# Black_Sesame.net
KiCad netlist of a schematic drawn in EAGLE
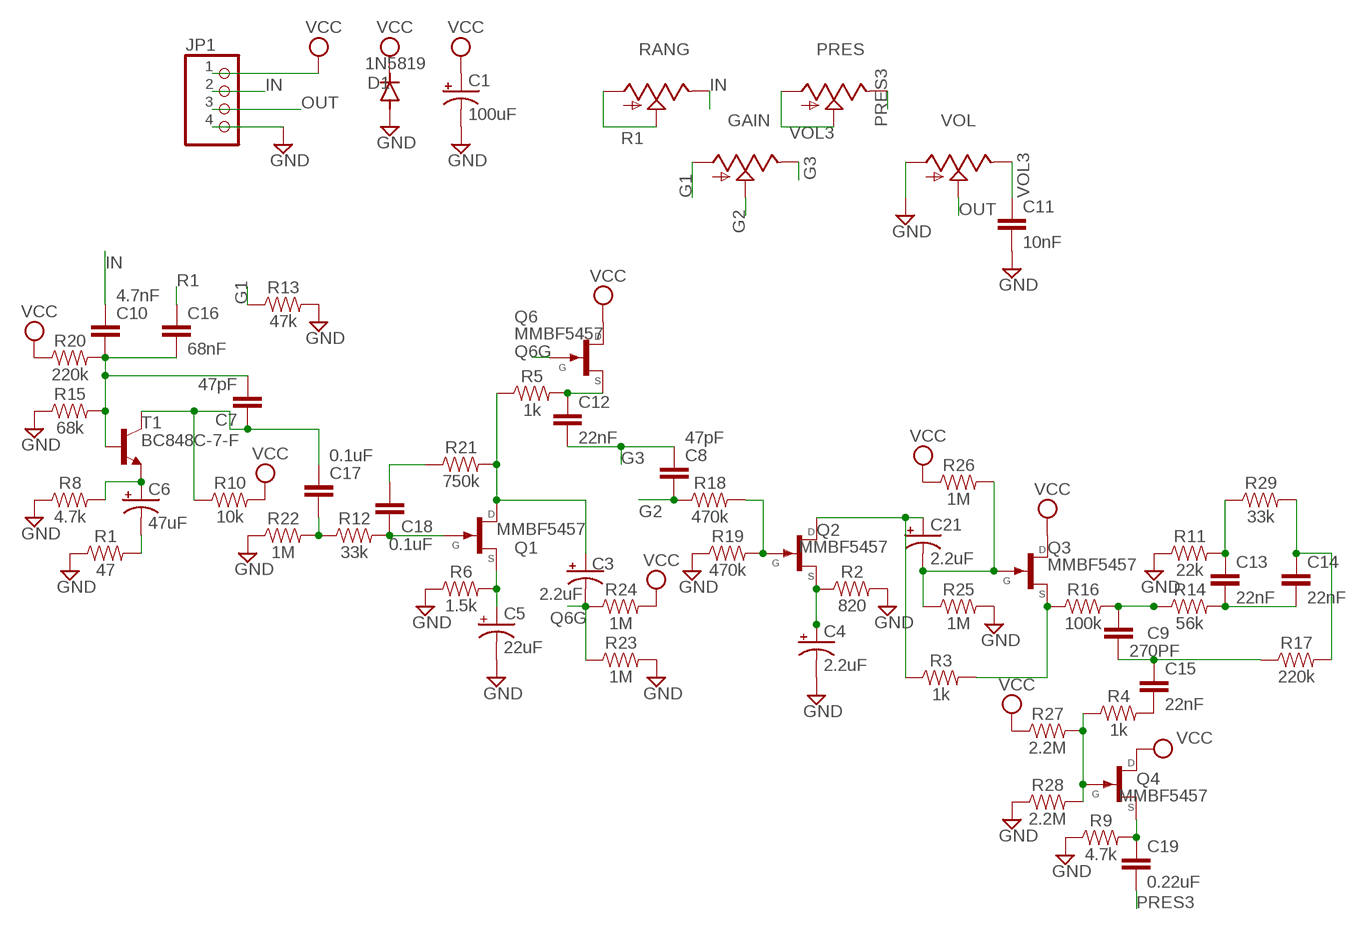
[diagram p0: schematic, sheet 1]

(export (version "E")
  (design (tool "Eeschema 10.0.6"))
  (components
    (comp (ref "C1")
      (value "100uF")
      (footprint "eagle-import:PAN_B_SMD+THRU")
      (libsource (lib "eagle-import") (part "CAP_SMD+THRUPAN_B"))
    )
    (comp (ref "C3")
      (value "2.2uF")
      (footprint "eagle-import:PAN_B_SMD+THRU")
      (libsource (lib "eagle-import") (part "CAP_SMD+THRUPAN_B"))
    )
    (comp (ref "C4")
      (value "2.2uF")
      (footprint "eagle-import:PAN_B_SMD+THRU")
      (libsource (lib "eagle-import") (part "CAP_SMD+THRUPAN_B"))
    )
    (comp (ref "C5")
      (value "22uF")
      (footprint "eagle-import:PAN_B_SMD+THRU")
      (libsource (lib "eagle-import") (part "CAP_SMD+THRUPAN_B"))
    )
    (comp (ref "C6")
      (value "47uF")
      (footprint "eagle-import:PAN_B_SMD+THRU")
      (libsource (lib "eagle-import") (part "CAP_SMD+THRUPAN_B"))
    )
    (comp (ref "C7")
      (value "47pF")
      (footprint "eagle-import:0603")
      (libsource (lib "eagle-import") (part "47PF-0603-50V-5%"))
    )
    (comp (ref "C8")
      (value "47pF")
      (footprint "eagle-import:0603")
      (libsource (lib "eagle-import") (part "47PF-0603-50V-5%"))
    )
    (comp (ref "C9")
      (value "270PF")
      (footprint "eagle-import:0603")
      (libsource (lib "eagle-import") (part "270PF-0603-50V-5%"))
    )
    (comp (ref "C10")
      (value "4.7nF")
      (footprint "eagle-import:0603")
      (libsource (lib "eagle-import") (part "3.3NF-0603-100V-10%"))
    )
    (comp (ref "C11")
      (value "10nF")
      (footprint "eagle-import:0603")
      (libsource (lib "eagle-import") (part "10NF-0603-50V-10%"))
    )
    (comp (ref "C12")
      (value "22nF")
      (footprint "eagle-import:0603")
      (libsource (lib "eagle-import") (part "22NF/22,000PF-0603-50V-10%"))
    )
    (comp (ref "C13")
      (value "22nF")
      (footprint "eagle-import:0603")
      (libsource (lib "eagle-import") (part "22NF/22,000PF-0603-50V-10%"))
    )
    (comp (ref "C14")
      (value "22nF")
      (footprint "eagle-import:0603")
      (libsource (lib "eagle-import") (part "22NF/22,000PF-0603-50V-10%"))
    )
    (comp (ref "C15")
      (value "22nF")
      (footprint "eagle-import:0603")
      (libsource (lib "eagle-import") (part "22NF/22,000PF-0603-50V-10%"))
    )
    (comp (ref "C16")
      (value "68nF")
      (footprint "eagle-import:0603")
      (libsource (lib "eagle-import") (part "47NF-0603-25V-5%"))
    )
    (comp (ref "C17")
      (value "0.1uF")
      (footprint "eagle-import:0603")
      (libsource (lib "eagle-import") (part "0.1UF-0603-25V-(+80/-20%)"))
    )
    (comp (ref "C18")
      (value "0.1uF")
      (footprint "eagle-import:0603")
      (libsource (lib "eagle-import") (part "0.1UF-0603-25V-(+80/-20%)"))
    )
    (comp (ref "C19")
      (value "0.22uF")
      (footprint "eagle-import:0603")
      (libsource (lib "eagle-import") (part "0.22UF-0603-25V-10%"))
    )
    (comp (ref "C21")
      (value "2.2uF")
      (footprint "eagle-import:PAN_B_SMD+THRU")
      (libsource (lib "eagle-import") (part "CAP_SMD+THRUPAN_B"))
    )
    (comp (ref "D1")
      (value "1N5819")
      (footprint "eagle-import:SOD123")
      (libsource (lib "eagle-import") (part "DIODE-SOD123"))
    )
    (comp (ref "GAIN")
      (value "9MM_SNAP-IN_POT_")
      (footprint "eagle-import:9MM_SNAP-IN_POT")
      (libsource (lib "eagle-import") (part "9MM_SNAP-IN_POT_"))
    )
    (comp (ref "JP1")
      (value "PINHD-1X4")
      (footprint "eagle-import:1X04")
      (libsource (lib "eagle-import") (part "PINHD-1X4"))
    )
    (comp (ref "PRES")
      (value "9MM_SNAP-IN_POT_")
      (footprint "eagle-import:9MM_SNAP-IN_POT")
      (libsource (lib "eagle-import") (part "9MM_SNAP-IN_POT_"))
    )
    (comp (ref "Q1")
      (value "MMBF5457")
      (footprint "eagle-import:SOT23")
      (fields (field (name "MF") "ON Semiconductor"))
      (libsource (lib "eagle-import") (part "MMBF5457"))
    )
    (comp (ref "Q2")
      (value "MMBF5457")
      (footprint "eagle-import:SOT23")
      (fields (field (name "MF") "ON Semiconductor"))
      (libsource (lib "eagle-import") (part "MMBF5457"))
    )
    (comp (ref "Q3")
      (value "MMBF5457")
      (footprint "eagle-import:SOT23")
      (fields (field (name "MF") "ON Semiconductor"))
      (libsource (lib "eagle-import") (part "MMBF5457"))
    )
    (comp (ref "Q4")
      (value "MMBF5457")
      (footprint "eagle-import:SOT23")
      (fields (field (name "MF") "ON Semiconductor"))
      (libsource (lib "eagle-import") (part "MMBF5457"))
    )
    (comp (ref "Q6")
      (value "MMBF5457")
      (footprint "eagle-import:SOT23")
      (fields (field (name "MF") "ON Semiconductor"))
      (libsource (lib "eagle-import") (part "MMBF5457"))
    )
    (comp (ref "R1")
      (value "47")
      (footprint "eagle-import:0603")
      (libsource (lib "eagle-import") (part "47KOHM-0603-1/10W-1%"))
    )
    (comp (ref "R2")
      (value "820")
      (footprint "eagle-import:0603")
      (libsource (lib "eagle-import") (part "82OHM-0603-1/10W-1%"))
    )
    (comp (ref "R3")
      (value "1k")
      (footprint "eagle-import:0603")
      (libsource (lib "eagle-import") (part "1KOHM-0603-1/10W-1%"))
    )
    (comp (ref "R4")
      (value "1k")
      (footprint "eagle-import:0603")
      (libsource (lib "eagle-import") (part "1KOHM-0603-1/10W-1%"))
    )
    (comp (ref "R5")
      (value "1k")
      (footprint "eagle-import:0603")
      (libsource (lib "eagle-import") (part "1KOHM-0603-1/10W-1%"))
    )
    (comp (ref "R6")
      (value "1.5k")
      (footprint "eagle-import:0603")
      (libsource (lib "eagle-import") (part "1KOHM-0603-1/10W-1%"))
    )
    (comp (ref "R8")
      (value "4.7k")
      (footprint "eagle-import:0603")
      (libsource (lib "eagle-import") (part "4.7KOHM-0603-1/10W-1%"))
    )
    (comp (ref "R9")
      (value "4.7k")
      (footprint "eagle-import:0603")
      (libsource (lib "eagle-import") (part "4.7KOHM-0603-1/10W-1%"))
    )
    (comp (ref "R10")
      (value "10k")
      (footprint "eagle-import:0603")
      (libsource (lib "eagle-import") (part "10KOHM-0603-1/10W-1%"))
    )
    (comp (ref "R11")
      (value "22k")
      (footprint "eagle-import:0603")
      (libsource (lib "eagle-import") (part "22KOHM-0603-1/10W-1%"))
    )
    (comp (ref "R12")
      (value "33k")
      (footprint "eagle-import:0603")
      (libsource (lib "eagle-import") (part "33KOHM-0603-1/10W-1%"))
    )
    (comp (ref "R13")
      (value "47k")
      (footprint "eagle-import:0603")
      (libsource (lib "eagle-import") (part "47KOHM-0603-1/10W-1%"))
    )
    (comp (ref "R14")
      (value "56k")
      (footprint "eagle-import:0603")
      (libsource (lib "eagle-import") (part "62KOHM-0603-1/10W-5%"))
    )
    (comp (ref "R15")
      (value "68k")
      (footprint "eagle-import:0603")
      (libsource (lib "eagle-import") (part "68.1KOHM-0603-1/10W-1%"))
    )
    (comp (ref "R16")
      (value "100k")
      (footprint "eagle-import:0603")
      (libsource (lib "eagle-import") (part "100KOHM-0603-1/10W-1%"))
    )
    (comp (ref "R17")
      (value "220k")
      (footprint "eagle-import:0603")
      (libsource (lib "eagle-import") (part "220KOHM-0603-1/10W-1%"))
    )
    (comp (ref "R18")
      (value "470k")
      (footprint "eagle-import:0603")
      (libsource (lib "eagle-import") (part "470OHM-0603-1/10W-1%"))
    )
    (comp (ref "R19")
      (value "470k")
      (footprint "eagle-import:0603")
      (libsource (lib "eagle-import") (part "470OHM-0603-1/10W-1%"))
    )
    (comp (ref "R20")
      (value "220k")
      (footprint "eagle-import:0603")
      (libsource (lib "eagle-import") (part "220KOHM-0603-1/10W-1%"))
    )
    (comp (ref "R21")
      (value "750k")
      (footprint "eagle-import:0603")
      (libsource (lib "eagle-import") (part "750OHM-0603-1/10W-1%"))
    )
    (comp (ref "R22")
      (value "1M")
      (footprint "eagle-import:0603")
      (libsource (lib "eagle-import") (part "1MOHM-0603-1/4W-5%"))
    )
    (comp (ref "R23")
      (value "1M")
      (footprint "eagle-import:0603")
      (libsource (lib "eagle-import") (part "1MOHM-0603-1/4W-5%"))
    )
    (comp (ref "R24")
      (value "1M")
      (footprint "eagle-import:0603")
      (libsource (lib "eagle-import") (part "1MOHM-0603-1/4W-5%"))
    )
    (comp (ref "R25")
      (value "1M")
      (footprint "eagle-import:0603")
      (libsource (lib "eagle-import") (part "1MOHM-0603-1/4W-5%"))
    )
    (comp (ref "R26")
      (value "1M")
      (footprint "eagle-import:0603")
      (libsource (lib "eagle-import") (part "1MOHM-0603-1/4W-5%"))
    )
    (comp (ref "R27")
      (value "2.2M")
      (footprint "eagle-import:0603")
      (libsource (lib "eagle-import") (part "2.2OHM-0603-1/10W-5%"))
    )
    (comp (ref "R28")
      (value "2.2M")
      (footprint "eagle-import:0603")
      (libsource (lib "eagle-import") (part "2.2OHM-0603-1/10W-5%"))
    )
    (comp (ref "R29")
      (value "33k")
      (footprint "eagle-import:0603")
      (libsource (lib "eagle-import") (part "33KOHM-0603-1/10W-1%"))
    )
    (comp (ref "RANG")
      (value "9MM_SNAP-IN_POT_")
      (footprint "eagle-import:9MM_SNAP-IN_POT")
      (libsource (lib "eagle-import") (part "9MM_SNAP-IN_POT_"))
    )
    (comp (ref "T1")
      (value "BC848C-7-F")
      (footprint "eagle-import:SOT23-BEC")
      (libsource (lib "eagle-import") (part "-NPN-SOT23-BECBC817-16"))
    )
    (comp (ref "VOL")
      (value "9MM_SNAP-IN_POT_")
      (footprint "eagle-import:9MM_SNAP-IN_POT")
      (libsource (lib "eagle-import") (part "9MM_SNAP-IN_POT_"))
    )
  )
  (nets
    (net (code "1") (name "/G1") (class "Default")
      (node (ref "GAIN") (pin "1") (pinfunction "A_1") (pintype "passive"))
      (node (ref "R13") (pin "1") (pinfunction "1_1") (pintype "passive"))
    )
    (net (code "2") (name "/G2") (class "Default")
      (node (ref "C8") (pin "2") (pinfunction "2_2") (pintype "passive"))
      (node (ref "GAIN") (pin "2") (pinfunction "S_2") (pintype "passive"))
      (node (ref "R18") (pin "1") (pinfunction "1_1") (pintype "passive"))
    )
    (net (code "3") (name "/G3") (class "Default")
      (node (ref "C12") (pin "2") (pinfunction "2_2") (pintype "passive"))
      (node (ref "C8") (pin "1") (pinfunction "1_1") (pintype "passive"))
      (node (ref "GAIN") (pin "3") (pinfunction "E_3") (pintype "passive"))
    )
    (net (code "4") (name "/IN") (class "Default")
      (node (ref "C10") (pin "1") (pinfunction "1_1") (pintype "passive"))
      (node (ref "JP1") (pin "2") (pinfunction "2_2") (pintype "passive"))
      (node (ref "RANG") (pin "3") (pinfunction "E_3") (pintype "passive"))
    )
    (net (code "5") (name "/OUT") (class "Default")
      (node (ref "JP1") (pin "3") (pinfunction "3_3") (pintype "passive"))
      (node (ref "VOL") (pin "2") (pinfunction "S_2") (pintype "passive"))
    )
    (net (code "6") (name "/PRES3") (class "Default")
      (node (ref "C19") (pin "2") (pinfunction "2_2") (pintype "passive"))
      (node (ref "PRES") (pin "3") (pinfunction "E_3") (pintype "passive"))
    )
    (net (code "7") (name "/Q6G") (class "Default")
      (node (ref "C3") (pin "-") (pinfunction "-_-") (pintype "passive"))
      (node (ref "C3") (pin "--") (pinfunction "-_--") (pintype "passive"))
      (node (ref "Q6") (pin "3") (pinfunction "G_3") (pintype "passive"))
      (node (ref "R23") (pin "1") (pinfunction "1_1") (pintype "passive"))
      (node (ref "R24") (pin "1") (pinfunction "1_1") (pintype "passive"))
    )
    (net (code "8") (name "/R1") (class "Default")
      (node (ref "C16") (pin "1") (pinfunction "1_1") (pintype "passive"))
      (node (ref "RANG") (pin "1") (pinfunction "A_1") (pintype "passive"))
      (node (ref "RANG") (pin "2") (pinfunction "S_2") (pintype "passive"))
    )
    (net (code "9") (name "/VOL3") (class "Default")
      (node (ref "C11") (pin "1") (pinfunction "1_1") (pintype "passive"))
      (node (ref "PRES") (pin "1") (pinfunction "A_1") (pintype "passive"))
      (node (ref "PRES") (pin "2") (pinfunction "S_2") (pintype "passive"))
      (node (ref "VOL") (pin "3") (pinfunction "E_3") (pintype "passive"))
    )
    (net (code "10") (name "GND") (class "Default")
      (node (ref "C1") (pin "-") (pinfunction "-_-") (pintype "passive"))
      (node (ref "C1") (pin "--") (pinfunction "-_--") (pintype "passive"))
      (node (ref "C11") (pin "2") (pinfunction "2_2") (pintype "passive"))
      (node (ref "C4") (pin "-") (pinfunction "-_-") (pintype "passive"))
      (node (ref "C4") (pin "--") (pinfunction "-_--") (pintype "passive"))
      (node (ref "C5") (pin "-") (pinfunction "-_-") (pintype "passive"))
      (node (ref "C5") (pin "--") (pinfunction "-_--") (pintype "passive"))
      (node (ref "D1") (pin "A") (pinfunction "A_A") (pintype "passive"))
      (node (ref "JP1") (pin "4") (pinfunction "4_4") (pintype "passive"))
      (node (ref "R1") (pin "1") (pinfunction "1_1") (pintype "passive"))
      (node (ref "R11") (pin "1") (pinfunction "1_1") (pintype "passive"))
      (node (ref "R13") (pin "2") (pinfunction "2_2") (pintype "passive"))
      (node (ref "R15") (pin "1") (pinfunction "1_1") (pintype "passive"))
      (node (ref "R19") (pin "1") (pinfunction "1_1") (pintype "passive"))
      (node (ref "R2") (pin "2") (pinfunction "2_2") (pintype "passive"))
      (node (ref "R22") (pin "1") (pinfunction "1_1") (pintype "passive"))
      (node (ref "R23") (pin "2") (pinfunction "2_2") (pintype "passive"))
      (node (ref "R25") (pin "2") (pinfunction "2_2") (pintype "passive"))
      (node (ref "R28") (pin "1") (pinfunction "1_1") (pintype "passive"))
      (node (ref "R6") (pin "1") (pinfunction "1_1") (pintype "passive"))
      (node (ref "R8") (pin "1") (pinfunction "1_1") (pintype "passive"))
      (node (ref "R9") (pin "1") (pinfunction "1_1") (pintype "passive"))
      (node (ref "VOL") (pin "1") (pinfunction "A_1") (pintype "passive"))
    )
    (net (code "11") (name "Net-(C6-+-Pad++)") (class "Default")
      (node (ref "C6") (pin "+") (pinfunction "+_+") (pintype "passive"))
      (node (ref "C6") (pin "++") (pinfunction "+_++") (pintype "passive"))
      (node (ref "R8") (pin "2") (pinfunction "2_2") (pintype "passive"))
      (node (ref "T1") (pin "E") (pinfunction "E_E") (pintype "passive"))
    )
    (net (code "12") (name "Net-(C6---Pad--)") (class "Default")
      (node (ref "C6") (pin "-") (pinfunction "-_-") (pintype "passive"))
      (node (ref "C6") (pin "--") (pinfunction "-_--") (pintype "passive"))
      (node (ref "R1") (pin "2") (pinfunction "2_2") (pintype "passive"))
    )
    (net (code "13") (name "Net-(C9-Pad1)") (class "Default")
      (node (ref "C9") (pin "1") (pinfunction "1_1") (pintype "passive"))
      (node (ref "R14") (pin "1") (pinfunction "1_1") (pintype "passive"))
      (node (ref "R16") (pin "2") (pinfunction "2_2") (pintype "passive"))
    )
    (net (code "14") (name "Net-(C10-Pad2)") (class "Default")
      (node (ref "C10") (pin "2") (pinfunction "2_2") (pintype "passive"))
      (node (ref "C16") (pin "2") (pinfunction "2_2") (pintype "passive"))
      (node (ref "C7") (pin "2") (pinfunction "2_2") (pintype "passive"))
      (node (ref "R15") (pin "2") (pinfunction "2_2") (pintype "passive"))
      (node (ref "R20") (pin "2") (pinfunction "2_2") (pintype "passive"))
      (node (ref "T1") (pin "B") (pinfunction "B_B") (pintype "passive"))
    )
    (net (code "15") (name "Net-(C13-Pad1)") (class "Default")
      (node (ref "C13") (pin "1") (pinfunction "1_1") (pintype "passive"))
      (node (ref "R11") (pin "2") (pinfunction "2_2") (pintype "passive"))
      (node (ref "R29") (pin "1") (pinfunction "1_1") (pintype "passive"))
    )
    (net (code "16") (name "Net-(C13-Pad2)") (class "Default")
      (node (ref "C13") (pin "2") (pinfunction "2_2") (pintype "passive"))
      (node (ref "C14") (pin "2") (pinfunction "2_2") (pintype "passive"))
      (node (ref "R14") (pin "2") (pinfunction "2_2") (pintype "passive"))
    )
    (net (code "17") (name "Net-(C14-Pad1)") (class "Default")
      (node (ref "C14") (pin "1") (pinfunction "1_1") (pintype "passive"))
      (node (ref "R17") (pin "2") (pinfunction "2_2") (pintype "passive"))
      (node (ref "R29") (pin "2") (pinfunction "2_2") (pintype "passive"))
    )
    (net (code "18") (name "Net-(C15-Pad1)") (class "Default")
      (node (ref "C15") (pin "1") (pinfunction "1_1") (pintype "passive"))
      (node (ref "C9") (pin "2") (pinfunction "2_2") (pintype "passive"))
      (node (ref "R17") (pin "1") (pinfunction "1_1") (pintype "passive"))
    )
    (net (code "19") (name "Net-(C15-Pad2)") (class "Default")
      (node (ref "C15") (pin "2") (pinfunction "2_2") (pintype "passive"))
      (node (ref "R4") (pin "2") (pinfunction "2_2") (pintype "passive"))
    )
    (net (code "20") (name "Net-(C17-Pad1)") (class "Default")
      (node (ref "C17") (pin "1") (pinfunction "1_1") (pintype "passive"))
      (node (ref "C7") (pin "1") (pinfunction "1_1") (pintype "passive"))
      (node (ref "R10") (pin "1") (pinfunction "1_1") (pintype "passive"))
      (node (ref "T1") (pin "C") (pinfunction "C_C") (pintype "passive"))
    )
    (net (code "21") (name "Net-(C17-Pad2)") (class "Default")
      (node (ref "C17") (pin "2") (pinfunction "2_2") (pintype "passive"))
      (node (ref "R12") (pin "1") (pinfunction "1_1") (pintype "passive"))
      (node (ref "R22") (pin "2") (pinfunction "2_2") (pintype "passive"))
    )
    (net (code "22") (name "Net-(C18-Pad2)") (class "Default")
      (node (ref "C18") (pin "2") (pinfunction "2_2") (pintype "passive"))
      (node (ref "R21") (pin "1") (pinfunction "1_1") (pintype "passive"))
    )
    (net (code "23") (name "Net-(Q1-D)") (class "Default")
      (node (ref "C3") (pin "+") (pinfunction "+_+") (pintype "passive"))
      (node (ref "C3") (pin "++") (pinfunction "+_++") (pintype "passive"))
      (node (ref "Q1") (pin "1") (pinfunction "D_1") (pintype "passive"))
      (node (ref "R21") (pin "2") (pinfunction "2_2") (pintype "passive"))
      (node (ref "R5") (pin "1") (pinfunction "1_1") (pintype "passive"))
    )
    (net (code "24") (name "Net-(Q1-G)") (class "Default")
      (node (ref "C18") (pin "1") (pinfunction "1_1") (pintype "passive"))
      (node (ref "Q1") (pin "3") (pinfunction "G_3") (pintype "passive"))
      (node (ref "R12") (pin "2") (pinfunction "2_2") (pintype "passive"))
    )
    (net (code "25") (name "Net-(Q1-S)") (class "Default")
      (node (ref "C5") (pin "+") (pinfunction "+_+") (pintype "passive"))
      (node (ref "C5") (pin "++") (pinfunction "+_++") (pintype "passive"))
      (node (ref "Q1") (pin "2") (pinfunction "S_2") (pintype "passive"))
      (node (ref "R6") (pin "2") (pinfunction "2_2") (pintype "passive"))
    )
    (net (code "26") (name "Net-(Q2-D)") (class "Default")
      (node (ref "C21") (pin "+") (pinfunction "+_+") (pintype "passive"))
      (node (ref "C21") (pin "++") (pinfunction "+_++") (pintype "passive"))
      (node (ref "Q2") (pin "1") (pinfunction "D_1") (pintype "passive"))
      (node (ref "R3") (pin "1") (pinfunction "1_1") (pintype "passive"))
    )
    (net (code "27") (name "Net-(Q2-G)") (class "Default")
      (node (ref "Q2") (pin "3") (pinfunction "G_3") (pintype "passive"))
      (node (ref "R18") (pin "2") (pinfunction "2_2") (pintype "passive"))
      (node (ref "R19") (pin "2") (pinfunction "2_2") (pintype "passive"))
    )
    (net (code "28") (name "Net-(Q2-S)") (class "Default")
      (node (ref "C4") (pin "+") (pinfunction "+_+") (pintype "passive"))
      (node (ref "C4") (pin "++") (pinfunction "+_++") (pintype "passive"))
      (node (ref "Q2") (pin "2") (pinfunction "S_2") (pintype "passive"))
      (node (ref "R2") (pin "1") (pinfunction "1_1") (pintype "passive"))
    )
    (net (code "29") (name "Net-(Q3-G)") (class "Default")
      (node (ref "C21") (pin "-") (pinfunction "-_-") (pintype "passive"))
      (node (ref "C21") (pin "--") (pinfunction "-_--") (pintype "passive"))
      (node (ref "Q3") (pin "3") (pinfunction "G_3") (pintype "passive"))
      (node (ref "R25") (pin "1") (pinfunction "1_1") (pintype "passive"))
      (node (ref "R26") (pin "2") (pinfunction "2_2") (pintype "passive"))
    )
    (net (code "30") (name "Net-(Q3-S)") (class "Default")
      (node (ref "Q3") (pin "2") (pinfunction "S_2") (pintype "passive"))
      (node (ref "R16") (pin "1") (pinfunction "1_1") (pintype "passive"))
      (node (ref "R3") (pin "2") (pinfunction "2_2") (pintype "passive"))
    )
    (net (code "31") (name "Net-(Q4-G)") (class "Default")
      (node (ref "Q4") (pin "3") (pinfunction "G_3") (pintype "passive"))
      (node (ref "R27") (pin "2") (pinfunction "2_2") (pintype "passive"))
      (node (ref "R28") (pin "2") (pinfunction "2_2") (pintype "passive"))
      (node (ref "R4") (pin "1") (pinfunction "1_1") (pintype "passive"))
    )
    (net (code "32") (name "Net-(Q4-S)") (class "Default")
      (node (ref "C19") (pin "1") (pinfunction "1_1") (pintype "passive"))
      (node (ref "Q4") (pin "2") (pinfunction "S_2") (pintype "passive"))
      (node (ref "R9") (pin "2") (pinfunction "2_2") (pintype "passive"))
    )
    (net (code "33") (name "Net-(Q6-S)") (class "Default")
      (node (ref "C12") (pin "1") (pinfunction "1_1") (pintype "passive"))
      (node (ref "Q6") (pin "2") (pinfunction "S_2") (pintype "passive"))
      (node (ref "R5") (pin "2") (pinfunction "2_2") (pintype "passive"))
    )
    (net (code "34") (name "VCC") (class "Default")
      (node (ref "C1") (pin "+") (pinfunction "+_+") (pintype "passive"))
      (node (ref "C1") (pin "++") (pinfunction "+_++") (pintype "passive"))
      (node (ref "D1") (pin "C") (pinfunction "C_C") (pintype "passive"))
      (node (ref "JP1") (pin "1") (pinfunction "1_1") (pintype "passive"))
      (node (ref "Q3") (pin "1") (pinfunction "D_1") (pintype "passive"))
      (node (ref "Q4") (pin "1") (pinfunction "D_1") (pintype "passive"))
      (node (ref "Q6") (pin "1") (pinfunction "D_1") (pintype "passive"))
      (node (ref "R10") (pin "2") (pinfunction "2_2") (pintype "passive"))
      (node (ref "R20") (pin "1") (pinfunction "1_1") (pintype "passive"))
      (node (ref "R24") (pin "2") (pinfunction "2_2") (pintype "passive"))
      (node (ref "R26") (pin "1") (pinfunction "1_1") (pintype "passive"))
      (node (ref "R27") (pin "1") (pinfunction "1_1") (pintype "passive"))
    )
  )
)
